# 10_Misc.net
KiCad netlist of a schematic drawn in Altium Designer
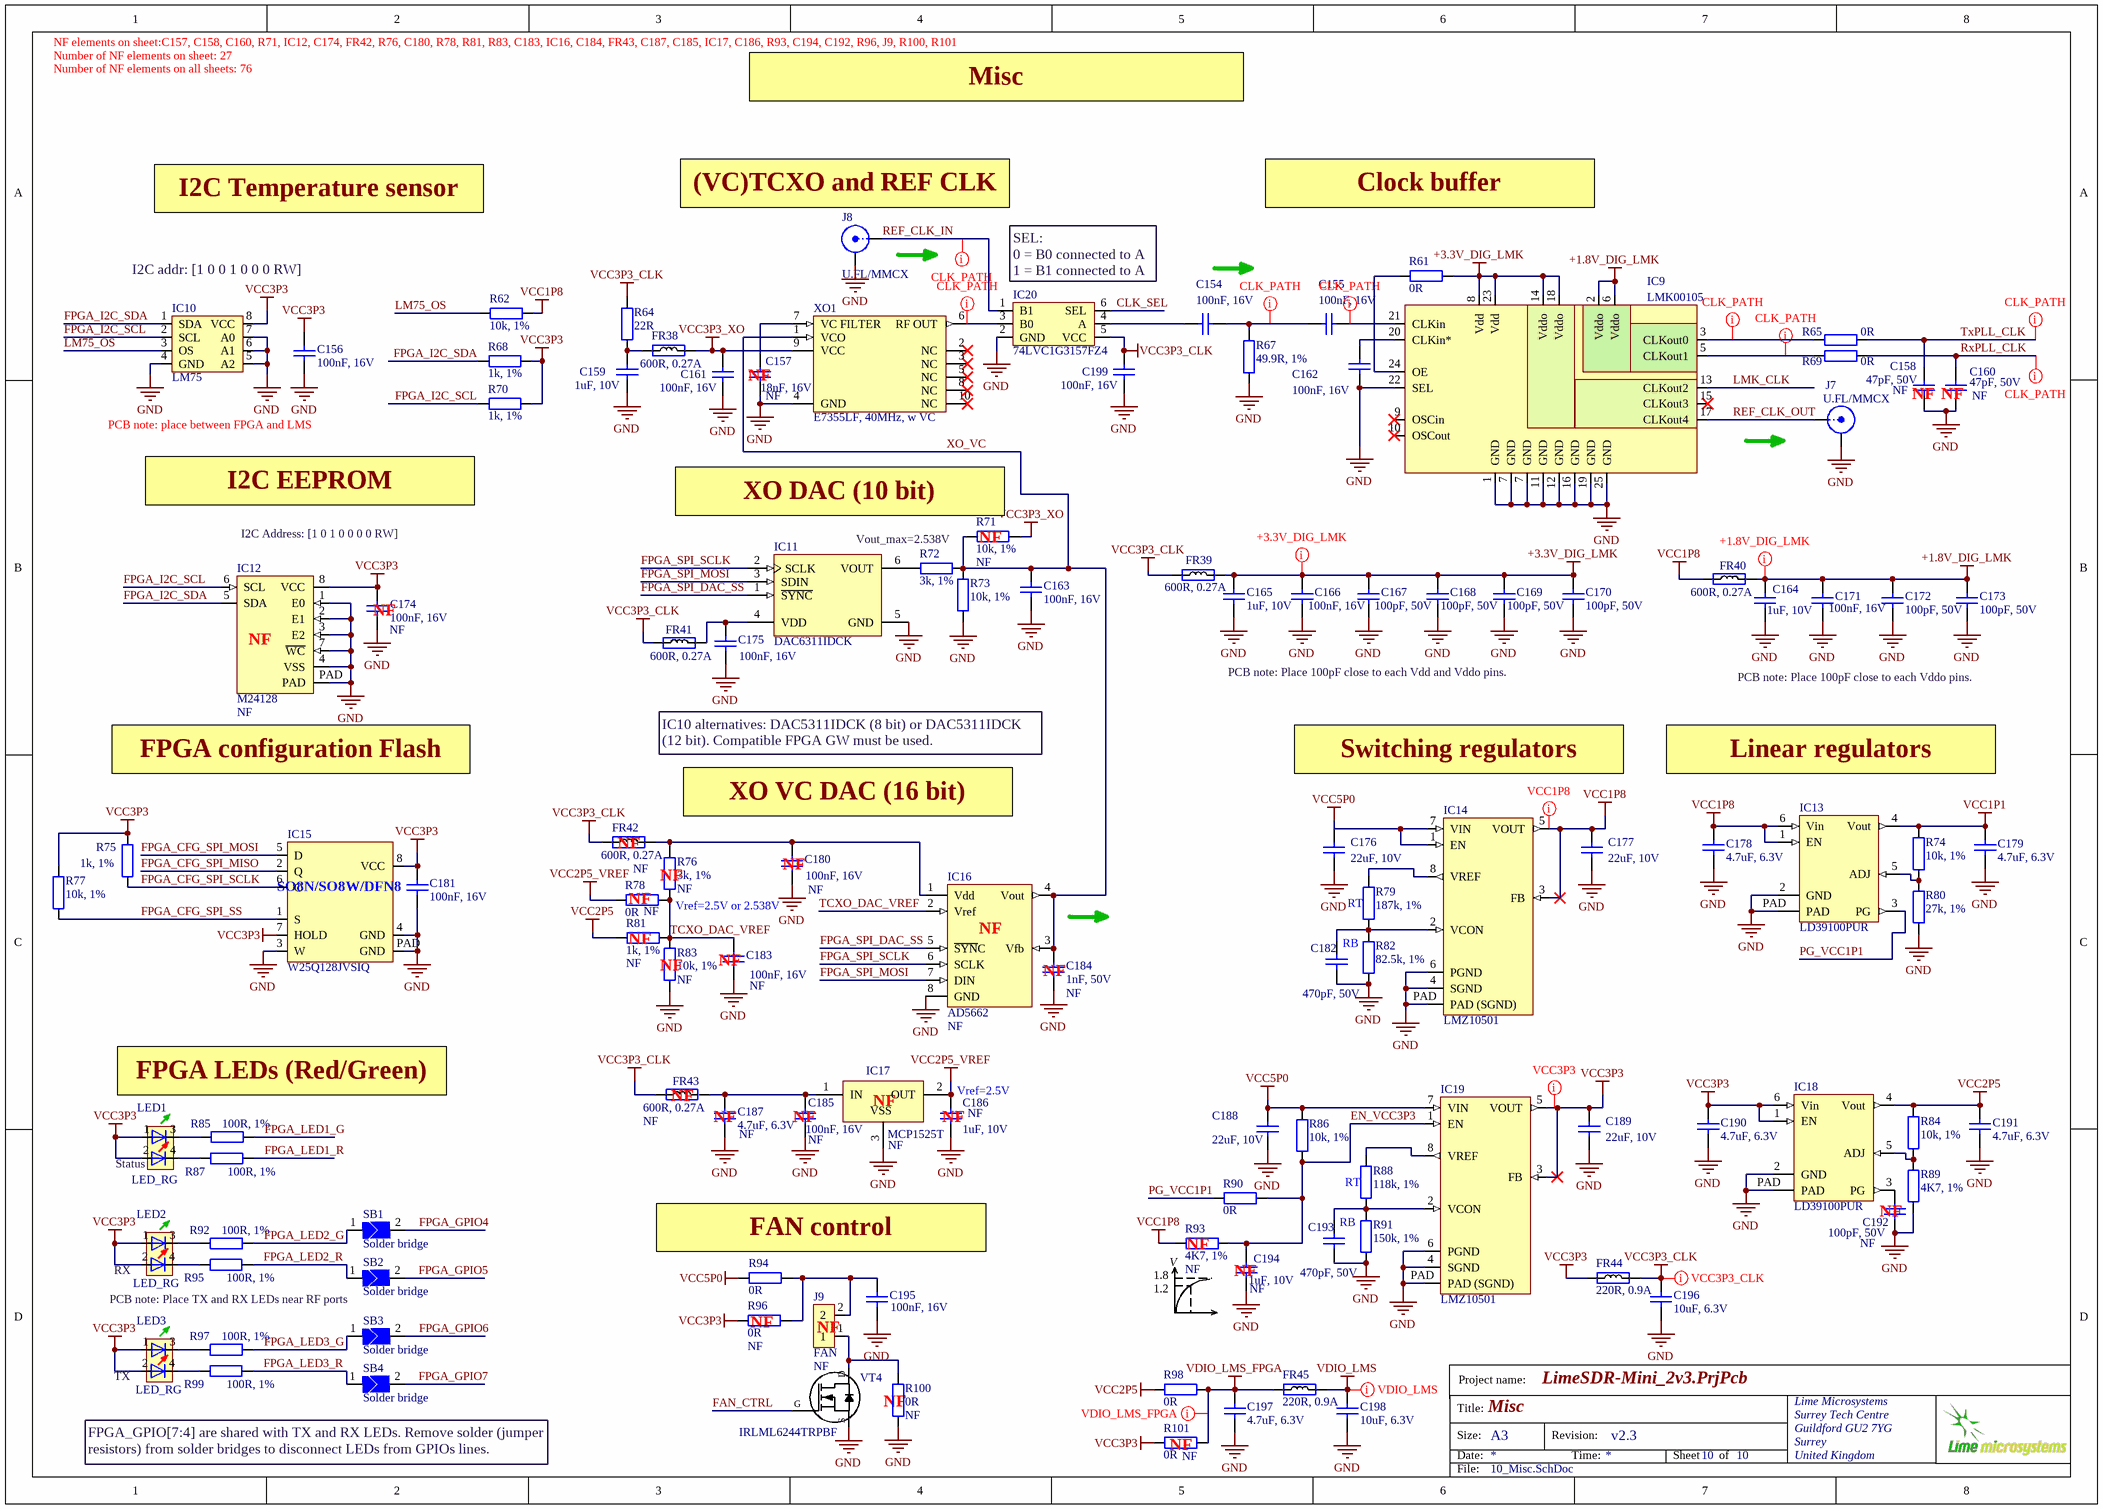
[diagram p0: 10_Misc.SchDoc]

(export (version "E")
  (design (tool "Eeschema 10.0.6"))
  (components
    (comp (ref "C154")
      (value "100nF, 16V")
      (footprint "CAP0402")
      (fields
        (field (name "MANUFACTURER") "Murata Electronics")
        (field (name "TOLERANCE") "10 %")
        (field (name "MANUFACTURER PART NUMBER") "GRM155R71C104KA88D")
      )
      (libsource (lib "LimeMicroAltiumLib_schLib") (part "Cap_0402"))
    )
    (comp (ref "C155")
      (value "100nF, 16V")
      (footprint "CAP0402")
      (fields
        (field (name "MANUFACTURER") "Murata Electronics")
        (field (name "TOLERANCE") "10 %")
        (field (name "MANUFACTURER PART NUMBER") "GRM155R71C104KA88D")
      )
      (libsource (lib "LimeMicroAltiumLib_schLib") (part "Cap_0402"))
    )
    (comp (ref "C156")
      (value "100nF, 16V")
      (footprint "CAP0402")
      (fields
        (field (name "TOLERANCE") "10 %")
        (field (name "MANUFACTURER") "Murata Electronics")
        (field (name "MANUFACTURER PART NUMBER") "GRM155R71C104KA88D")
      )
      (libsource (lib "LimeFPGAboard_schLib") (part "Cap_0603"))
    )
    (comp (ref "C157")
      (value "18nF, 16V")
      (footprint "CAP0402")
      (fields
        (field (name "ASSEMBLY INFO") "NF")
        (field (name "MANUFACTURER") "Yageo")
        (field (name "TOLERANCE") "±10%")
      )
      (libsource (lib "LimeMicroAltiumLib_schLib") (part "Cap_0402"))
    )
    (comp (ref "C158")
      (value "47pF, 50V")
      (footprint "CAP0402")
      (fields
        (field (name "TOLERANCE") "±1%")
        (field (name "MANUFACTURER") "TDK Corporation")
        (field (name "ASSEMBLY INFO") "NF")
      )
      (libsource (lib "LimeMicroAltiumLib_schLib") (part "Cap_0402"))
    )
    (comp (ref "C159")
      (value "1uF, 10V")
      (footprint "CAP0402")
      (fields (field (name "MANUFACTURER") "TDK"))
      (libsource (lib "LimeMicroAltiumLib_schLib") (part "Cap_0402"))
    )
    (comp (ref "C160")
      (value "47pF, 50V")
      (footprint "CAP0402")
      (fields
        (field (name "TOLERANCE") "±1%")
        (field (name "MANUFACTURER") "TDK Corporation")
        (field (name "ASSEMBLY INFO") "NF")
      )
      (libsource (lib "LimeMicroAltiumLib_schLib") (part "Cap_0402"))
    )
    (comp (ref "C161")
      (value "100nF, 16V")
      (footprint "CAP0402")
      (fields
        (field (name "MANUFACTURER") "Murata Electronics")
        (field (name "TOLERANCE") "10 %")
        (field (name "MANUFACTURER PART NUMBER") "GRM155R71C104KA88D")
      )
      (libsource (lib "LimeMicroAltiumLib_schLib") (part "Cap_0402"))
    )
    (comp (ref "C162")
      (value "100nF, 16V")
      (footprint "CAP0402")
      (fields
        (field (name "MANUFACTURER") "Murata Electronics")
        (field (name "TOLERANCE") "10 %")
        (field (name "MANUFACTURER PART NUMBER") "GRM155R71C104KA88D")
      )
      (libsource (lib "LimeMicroAltiumLib_schLib") (part "Cap_0402"))
    )
    (comp (ref "C163")
      (value "100nF, 16V")
      (footprint "CAP0402")
      (fields
        (field (name "MANUFACTURER") "Murata Electronics")
        (field (name "TOLERANCE") "10 %")
        (field (name "MANUFACTURER PART NUMBER") "GRM155R71C104KA88D")
      )
      (libsource (lib "LimeMicroAltiumLib_schLib") (part "Cap_0402"))
    )
    (comp (ref "C164")
      (value "1uF, 10V")
      (footprint "CAP0402")
      (fields (field (name "MANUFACTURER") "TDK"))
      (libsource (lib "LimeMicroAltiumLib_schLib") (part "Cap_0402"))
    )
    (comp (ref "C165")
      (value "1uF, 10V")
      (footprint "CAP0402")
      (fields (field (name "MANUFACTURER") "TDK"))
      (libsource (lib "LimeMicroAltiumLib_schLib") (part "Cap_0402"))
    )
    (comp (ref "C166")
      (value "100nF, 16V")
      (footprint "CAP0402")
      (fields
        (field (name "MANUFACTURER") "Murata Electronics")
        (field (name "TOLERANCE") "10 %")
        (field (name "MANUFACTURER PART NUMBER") "GRM155R71C104KA88D")
      )
      (libsource (lib "LimeMicroAltiumLib_schLib") (part "Cap_0402"))
    )
    (comp (ref "C167")
      (value "100pF, 50V")
      (footprint "CAP0402")
      (fields (field (name "MANUFACTURER") "Yageo") (field (name "TOLERANCE") "±5%"))
      (libsource (lib "LimeMicroAltiumLib_schLib") (part "Cap_0402"))
    )
    (comp (ref "C168")
      (value "100pF, 50V")
      (footprint "CAP0402")
      (fields (field (name "MANUFACTURER") "Yageo") (field (name "TOLERANCE") "±5%"))
      (libsource (lib "LimeMicroAltiumLib_schLib") (part "Cap_0402"))
    )
    (comp (ref "C169")
      (value "100pF, 50V")
      (footprint "CAP0402")
      (fields (field (name "MANUFACTURER") "Yageo") (field (name "TOLERANCE") "±5%"))
      (libsource (lib "LimeMicroAltiumLib_schLib") (part "Cap_0402"))
    )
    (comp (ref "C170")
      (value "100pF, 50V")
      (footprint "CAP0402")
      (fields (field (name "MANUFACTURER") "Yageo") (field (name "TOLERANCE") "±5%"))
      (libsource (lib "LimeMicroAltiumLib_schLib") (part "Cap_0402"))
    )
    (comp (ref "C171")
      (value "100nF, 16V")
      (footprint "CAP0402")
      (fields
        (field (name "MANUFACTURER") "Murata Electronics")
        (field (name "TOLERANCE") "10 %")
        (field (name "MANUFACTURER PART NUMBER") "GRM155R71C104KA88D")
      )
      (libsource (lib "LimeMicroAltiumLib_schLib") (part "Cap_0402"))
    )
    (comp (ref "C172")
      (value "100pF, 50V")
      (footprint "CAP0402")
      (fields (field (name "MANUFACTURER") "Yageo") (field (name "TOLERANCE") "±5%"))
      (libsource (lib "LimeMicroAltiumLib_schLib") (part "Cap_0402"))
    )
    (comp (ref "C173")
      (value "100pF, 50V")
      (footprint "CAP0402")
      (fields (field (name "MANUFACTURER") "Yageo") (field (name "TOLERANCE") "±5%"))
      (libsource (lib "LimeMicroAltiumLib_schLib") (part "Cap_0402"))
    )
    (comp (ref "C174")
      (value "100nF, 16V")
      (footprint "CAP0402")
      (fields
        (field (name "TOLERANCE") "10 %")
        (field (name "MANUFACTURER") "Murata Electronics")
        (field (name "MANUFACTURER PART NUMBER") "GRM155R71C104KA88D")
        (field (name "ASSEMBLY INFO") "NF")
      )
      (libsource (lib "LimeFPGAboard_schLib") (part "Cap_0603"))
    )
    (comp (ref "C175")
      (value "100nF, 16V")
      (footprint "CAP0402")
      (fields
        (field (name "TOLERANCE") "10 %")
        (field (name "MANUFACTURER") "Murata Electronics")
        (field (name "MANUFACTURER PART NUMBER") "GRM155R71C104KA88D")
      )
      (libsource (lib "LimeFPGAboard_schLib") (part "Cap_0603"))
    )
    (comp (ref "C176")
      (value "22uF, 10V")
      (footprint "CAP0603")
      (fields (field (name "TOLERANCE") "20 %") (field (name "MANUFACTURER") "TDK Corporation"))
      (libsource (lib "LimeFPGAboard_schLib") (part "Cap_0603"))
    )
    (comp (ref "C177")
      (value "22uF, 10V")
      (footprint "CAP0603")
      (fields (field (name "TOLERANCE") "20 %") (field (name "MANUFACTURER") "TDK Corporation"))
      (libsource (lib "LimeFPGAboard_schLib") (part "Cap_0603"))
    )
    (comp (ref "C178")
      (value "4.7uF, 6.3V")
      (footprint "CAP0402")
      (fields
        (field (name "MANUFACTURER") "Murata Electronics North America")
        (field (name "TOLERANCE") "±20%")
      )
      (libsource (lib "LimeMicroAltiumLib_schLib") (part "Cap_0402"))
    )
    (comp (ref "C179")
      (value "4.7uF, 6.3V")
      (footprint "CAP0402")
      (fields
        (field (name "MANUFACTURER") "Murata Electronics North America")
        (field (name "TOLERANCE") "±20%")
      )
      (libsource (lib "LimeMicroAltiumLib_schLib") (part "Cap_0402"))
    )
    (comp (ref "C180")
      (value "100nF, 16V")
      (footprint "CAP0402")
      (fields
        (field (name "TOLERANCE") "10 %")
        (field (name "MANUFACTURER") "Murata Electronics")
        (field (name "MANUFACTURER PART NUMBER") "GRM155R71C104KA88D")
        (field (name "ASSEMBLY INFO") "NF")
      )
      (libsource (lib "LimeFPGAboard_schLib") (part "Cap_0603"))
    )
    (comp (ref "C181")
      (value "100nF, 16V")
      (footprint "CAP0402")
      (fields
        (field (name "TOLERANCE") "10 %")
        (field (name "MANUFACTURER") "Murata Electronics")
        (field (name "MANUFACTURER PART NUMBER") "GRM155R71C104KA88D")
      )
      (libsource (lib "LimeFPGAboard_schLib") (part "Cap_0603"))
    )
    (comp (ref "C182")
      (value "470pF, 50V")
      (footprint "CAP0402")
      (fields (field (name "TOLERANCE") "±5%") (field (name "MANUFACTURER") "TDK Corporation"))
      (libsource (lib "LimeMicroAltiumLib_schLib") (part "Cap_0402"))
    )
    (comp (ref "C183")
      (value "100nF, 16V")
      (footprint "CAP0402")
      (fields
        (field (name "TOLERANCE") "10 %")
        (field (name "MANUFACTURER") "Murata Electronics")
        (field (name "ASSEMBLY INFO") "NF")
      )
      (libsource (lib "") (part "Cap_0603_1"))
    )
    (comp (ref "C184")
      (value "1nF, 50V")
      (footprint "CAP0402")
      (fields
        (field (name "ASSEMBLY INFO") "NF")
        (field (name "TOLERANCE") "10 %")
        (field (name "MANUFACTURER") "Murata Electronics")
      )
      (libsource (lib "") (part "Cap_0402_1"))
    )
    (comp (ref "C185")
      (value "100nF, 16V")
      (footprint "CAP0402")
      (fields
        (field (name "TOLERANCE") "10 %")
        (field (name "MANUFACTURER") "Murata Electronics")
        (field (name "ASSEMBLY INFO") "NF")
      )
      (libsource (lib "") (part "Cap_0603_1"))
    )
    (comp (ref "C186")
      (value "1uF, 10V")
      (footprint "CAP0402")
      (fields (field (name "ASSEMBLY INFO") "NF") (field (name "MANUFACTURER") "TDK"))
      (libsource (lib "LimeMicroAltiumLib_schLib") (part "Cap_0402"))
    )
    (comp (ref "C187")
      (value "4.7uF, 6.3V")
      (footprint "CAP0402")
      (fields
        (field (name "ASSEMBLY INFO") "NF")
        (field (name "MANUFACTURER") "Murata Electronics North America")
        (field (name "TOLERANCE") "±20%")
      )
      (libsource (lib "LimeMicroAltiumLib_schLib") (part "Cap_0402"))
    )
    (comp (ref "C188")
      (value "22uF, 10V")
      (footprint "CAP0603")
      (fields (field (name "TOLERANCE") "20 %") (field (name "MANUFACTURER") "TDK Corporation"))
      (libsource (lib "LimeFPGAboard_schLib") (part "Cap_0603"))
    )
    (comp (ref "C189")
      (value "22uF, 10V")
      (footprint "CAP0603")
      (fields (field (name "TOLERANCE") "20 %") (field (name "MANUFACTURER") "TDK Corporation"))
      (libsource (lib "LimeFPGAboard_schLib") (part "Cap_0603"))
    )
    (comp (ref "C190")
      (value "4.7uF, 6.3V")
      (footprint "CAP0402")
      (fields
        (field (name "MANUFACTURER") "Murata Electronics North America")
        (field (name "TOLERANCE") "±20%")
      )
      (libsource (lib "LimeMicroAltiumLib_schLib") (part "Cap_0402"))
    )
    (comp (ref "C191")
      (value "4.7uF, 6.3V")
      (footprint "CAP0402")
      (fields
        (field (name "MANUFACTURER") "Murata Electronics North America")
        (field (name "TOLERANCE") "±20%")
      )
      (libsource (lib "LimeMicroAltiumLib_schLib") (part "Cap_0402"))
    )
    (comp (ref "C192")
      (value "100pF, 50V")
      (footprint "CAP0402")
      (fields
        (field (name "ASSEMBLY INFO") "NF")
        (field (name "MANUFACTURER") "Yageo")
        (field (name "TOLERANCE") "±5%")
      )
      (libsource (lib "LimeMicroAltiumLib_schLib") (part "Cap_0402"))
    )
    (comp (ref "C193")
      (value "470pF, 50V")
      (footprint "CAP0402")
      (fields (field (name "TOLERANCE") "±5%") (field (name "MANUFACTURER") "TDK Corporation"))
      (libsource (lib "LimeMicroAltiumLib_schLib") (part "Cap_0402"))
    )
    (comp (ref "C194")
      (value "1uF, 10V")
      (footprint "CAP0402")
      (fields (field (name "ASSEMBLY INFO") "NF") (field (name "MANUFACTURER") "TDK"))
      (libsource (lib "LimeMicroAltiumLib_schLib") (part "Cap_0402"))
    )
    (comp (ref "C195")
      (value "100nF, 16V")
      (footprint "CAP0402")
      (fields
        (field (name "TOLERANCE") "10 %")
        (field (name "MANUFACTURER") "Murata Electronics")
        (field (name "MANUFACTURER PART NUMBER") "GRM155R71C104KA88D")
      )
      (libsource (lib "LimeFPGAboard_schLib") (part "Cap_0603"))
    )
    (comp (ref "C196")
      (value "10uF, 6.3V")
      (footprint "CAP0603")
      (fields (field (name "TOLERANCE") "±20%") (field (name "MANUFACTURER") "Yageo"))
      (libsource (lib "LimeFPGAboard_schLib") (part "Cap_0603"))
    )
    (comp (ref "C197")
      (value "4.7uF, 6.3V")
      (footprint "CAP0402")
      (fields
        (field (name "MANUFACTURER") "Murata Electronics North America")
        (field (name "TOLERANCE") "±20%")
      )
      (libsource (lib "LimeMicroAltiumLib_schLib") (part "Cap_0402"))
    )
    (comp (ref "C198")
      (value "10uF, 6.3V")
      (footprint "CAP0603")
      (fields (field (name "TOLERANCE") "±20%") (field (name "MANUFACTURER") "Yageo"))
      (libsource (lib "LimeFPGAboard_schLib") (part "Cap_0603"))
    )
    (comp (ref "C199")
      (value "100nF, 16V")
      (footprint "CAP0402")
      (fields
        (field (name "MANUFACTURER") "Murata Electronics")
        (field (name "TOLERANCE") "10 %")
        (field (name "MANUFACTURER PART NUMBER") "GRM155R71C104KA88D")
      )
      (libsource (lib "LimeMicroAltiumLib_schLib") (part "Cap_0402"))
    )
    (comp (ref "FR38")
      (value "600R, 0.27A")
      (footprint "RES0201")
      (fields (field (name "MANUFACTURER") "Taiyo Yuden"))
      (libsource (lib "LimeMicroAltiumLib_schLib") (part "Ferrite"))
    )
    (comp (ref "FR39")
      (value "600R, 0.27A")
      (footprint "RES0201")
      (fields (field (name "MANUFACTURER") "Taiyo Yuden"))
      (libsource (lib "LimeMicroAltiumLib_schLib") (part "Ferrite"))
    )
    (comp (ref "FR40")
      (value "600R, 0.27A")
      (footprint "RES0201")
      (fields (field (name "MANUFACTURER") "Taiyo Yuden"))
      (libsource (lib "LimeMicroAltiumLib_schLib") (part "Ferrite"))
    )
    (comp (ref "FR41")
      (value "600R, 0.27A")
      (footprint "RES0201")
      (fields (field (name "MANUFACTURER") "Taiyo Yuden"))
      (libsource (lib "LimeMicroAltiumLib_schLib") (part "Ferrite"))
    )
    (comp (ref "FR42")
      (value "600R, 0.27A")
      (footprint "RES0201")
      (fields (field (name "MANUFACTURER") "Taiyo Yuden") (field (name "ASSEMBLY INFO") "NF"))
      (libsource (lib "LimeMicroAltiumLib_schLib") (part "Ferrite"))
    )
    (comp (ref "FR43")
      (value "600R, 0.27A")
      (footprint "RES0201")
      (fields (field (name "MANUFACTURER") "Taiyo Yuden") (field (name "ASSEMBLY INFO") "NF"))
      (libsource (lib "LimeMicroAltiumLib_schLib") (part "Ferrite"))
    )
    (comp (ref "FR44")
      (value "220R, 0.9A")
      (footprint "RES0402")
      (fields (field (name "MANUFACTURER") "TDK Corporation"))
      (libsource (lib "LimeFPGAboard_schLib") (part "Ferrite"))
    )
    (comp (ref "FR45")
      (value "220R, 0.9A")
      (footprint "RES0402")
      (fields (field (name "MANUFACTURER") "TDK Corporation"))
      (libsource (lib "LimeFPGAboard_schLib") (part "Ferrite"))
    )
    (comp (ref "IC9")
      (value "LMK00105")
      (footprint "LMK00105SQ")
      (fields (field (name "MANUFACTURER") "Texas Instruments"))
      (libsource (lib "LimeMicroAltiumLib_schLib") (part "LMK00105"))
    )
    (comp (ref "IC10")
      (value "LM75")
      (footprint "HWSON8_LM75")
      (fields (field (name "MANUFACTURER") "NXP Semiconductors"))
      (libsource (lib "LimeMicroAltiumLib_schLib") (part "LM75"))
    )
    (comp (ref "IC11")
      (value "DAC6311IDCK")
      (footprint "AD5601_SOT23-6")
      (fields (field (name "MANUFACTURER") "Texas Instruments"))
      (libsource (lib "LimeMicroAltiumLib_schLib") (part "AD5601BKSZ-REEL7"))
    )
    (comp (ref "IC12")
      (value "M24128")
      (footprint "M24128-DFMC6TG")
      (fields (field (name "MANUFACTURER") "STMicroelectronics") (field (name "ASSEMBLY INFO") "NF"))
      (libsource (lib "LimeMicroAltiumLib_schLib") (part "M24128-DFMC6TG"))
    )
    (comp (ref "IC13")
      (value "LD39100PUR")
      (footprint "LD39100PUR")
      (fields (field (name "MANUFACTURER") "STMicroelectronics"))
      (libsource (lib "LimeMicroAltiumLib_schLib") (part "LD39100PUR"))
    )
    (comp (ref "IC14")
      (value "LMZ10501")
      (footprint "LMZ10501")
      (fields (field (name "MANUFACTURER") "Texas Instruments"))
      (libsource (lib "LimeMicroAltiumLib_schLib") (part "LMZ10501"))
    )
    (comp (ref "IC15")
      (value "W25Q128JVSIQ")
      (footprint "S25FL164K_WSON8_DFN6")
      (fields (field (name "MANUFACTURER") "Winbond"))
      (libsource (lib "LimeMicroAltiumLib_schLib_r03") (part "M25P40_with_pad"))
    )
    (comp (ref "IC16")
      (value "AD5662")
      (footprint "AD5662_SOT23-8")
      (fields (field (name "MANUFACTURER") "Analog Devices Inc.") (field (name "ASSEMBLY INFO") "NF"))
      (libsource (lib "LimeMicroAltiumLib_schLib") (part "AD5662"))
    )
    (comp (ref "IC17")
      (value "MCP1525T")
      (footprint "SOT23-3_v2")
      (description "2.5V Voltage Reference, 3-Pin SOT-23, Industrial Temperature, Tape and Reel")
      (fields
        (field (name "MANUFACTURER") "Microchip Technology")
        (field (name "TOLERANCE") "±1%")
        (field (name "ASSEMBLY INFO") "NF")
      )
      (libsource (lib "LimeMicroAltiumLib_schLib") (part "MCP1525T-I/TT"))
    )
    (comp (ref "IC18")
      (value "LD39100PUR")
      (footprint "LD39100PUR")
      (fields (field (name "MANUFACTURER") "STMicroelectronics"))
      (libsource (lib "LimeMicroAltiumLib_schLib") (part "LD39100PUR"))
    )
    (comp (ref "IC19")
      (value "LMZ10501")
      (footprint "LMZ10501")
      (fields (field (name "MANUFACTURER") "Texas Instruments"))
      (libsource (lib "LimeMicroAltiumLib_schLib") (part "LMZ10501"))
    )
    (comp (ref "IC20")
      (value "74LVC1G3157FZ4")
      (footprint "74LVC1G3157FZ4_SPDT_SW_DFN1410-6")
      (fields (field (name "MANUFACTURER") "Diodes"))
      (libsource (lib "LimeMicroAltiumLib_schLib_r04") (part "74LVC1G3157FZ4_SPDT_SW"))
    )
    (comp (ref "J7")
      (value "U.FL/MMCX")
      (footprint "MMCX_UFL_conn_u")
      (description "CONN UMC RCPT STR 50 OHM SMD")
      (fields (field (name "MANUFACTURER") "Molex, LLC"))
      (libsource (lib "LimeMicroAltiumLib_schLib") (part "RF_IF_connector"))
    )
    (comp (ref "J8")
      (value "U.FL/MMCX")
      (footprint "MMCX_UFL_conn_u")
      (description "CONN UMC RCPT STR 50 OHM SMD")
      (fields (field (name "MANUFACTURER") "Molex, LLC"))
      (libsource (lib "LimeMicroAltiumLib_schLib") (part "RF_IF_connector"))
    )
    (comp (ref "J9")
      (value "FAN")
      (footprint "Header2x1_TH_v2")
      (fields (field (name "ASSEMBLY INFO") "NF") (field (name "MANUFACTURER") "3M"))
      (libsource (lib "LimeFPGAboard_schLib") (part "Jumper"))
    )
    (comp (ref "LED1")
      (value "LED_RG")
      (footprint "LED-2x0603")
      (fields (field (name "MANUFACTURER") "Avago Technologies US Inc."))
      (libsource (lib "LimeMicroAltiumLib_schLib") (part "LED_green_red_SMD"))
    )
    (comp (ref "LED2")
      (value "LED_RG")
      (footprint "LED-2x0603")
      (fields (field (name "MANUFACTURER") "Avago Technologies US Inc."))
      (libsource (lib "LimeMicroAltiumLib_schLib") (part "LED_green_red_SMD"))
    )
    (comp (ref "LED3")
      (value "LED_RG")
      (footprint "LED-2x0603")
      (fields (field (name "MANUFACTURER") "Avago Technologies US Inc."))
      (libsource (lib "LimeMicroAltiumLib_schLib") (part "LED_green_red_SMD"))
    )
    (comp (ref "R61")
      (value "0R")
      (footprint "RES0402")
      (fields (field (name "MANUFACTURER") "Yageo") (field (name "TOLERANCE") "Jumper"))
      (libsource (lib "LimeMicroAltiumLib_schLib") (part "Res_0402"))
    )
    (comp (ref "R62")
      (value "10k, 1%")
      (footprint "RES0402")
      (fields (field (name "MANUFACTURER") "Yageo") (field (name "TOLERANCE") "±1%"))
      (libsource (lib "LimeMicroAltiumLib_schLib") (part "Res_0402"))
    )
    (comp (ref "R64")
      (value "22R")
      (footprint "RES0402")
      (fields (field (name "TOLERANCE") "±1%") (field (name "MANUFACTURER") "Yageo"))
      (libsource (lib "LimeFPGAboard_schLib") (part "Res_0402"))
    )
    (comp (ref "R65")
      (value "0R")
      (footprint "RES0402")
      (fields (field (name "MANUFACTURER") "Yageo") (field (name "TOLERANCE") "Jumper"))
      (libsource (lib "LimeFPGAboard_schLib") (part "Res_0402"))
    )
    (comp (ref "R67")
      (value "49.9R, 1%")
      (footprint "RES0402")
      (fields
        (field (name "TOLERANCE") "±1%")
        (field (name "MANUFACTURER") "Samsung Electro-Mechanics America, Inc.")
      )
      (libsource (lib "LimeMicroAltiumLib_schLib") (part "Res_0402"))
    )
    (comp (ref "R68")
      (value "1k, 1%")
      (footprint "RES0402")
      (fields (field (name "MANUFACTURER") "Stackpole Electronics Inc") (field (name "TOLERANCE") "±1%"))
      (libsource (lib "LimeMicroAltiumLib_schLib") (part "Res_0402"))
    )
    (comp (ref "R69")
      (value "0R")
      (footprint "RES0402")
      (fields (field (name "MANUFACTURER") "Yageo") (field (name "TOLERANCE") "Jumper"))
      (libsource (lib "LimeFPGAboard_schLib") (part "Res_0402"))
    )
    (comp (ref "R70")
      (value "1k, 1%")
      (footprint "RES0402")
      (fields (field (name "MANUFACTURER") "Stackpole Electronics Inc") (field (name "TOLERANCE") "±1%"))
      (libsource (lib "LimeMicroAltiumLib_schLib") (part "Res_0402"))
    )
    (comp (ref "R71")
      (value "10k, 1%")
      (footprint "RES0402")
      (fields
        (field (name "ASSEMBLY INFO") "NF")
        (field (name "MANUFACTURER") "Yageo")
        (field (name "TOLERANCE") "±1%")
      )
      (libsource (lib "LimeMicroAltiumLib_schLib") (part "Res_0402"))
    )
    (comp (ref "R72")
      (value "3k, 1%")
      (footprint "RES0402")
      (fields (field (name "TOLERANCE") "±1%") (field (name "MANUFACTURER") "Vishay Dale"))
      (libsource (lib "LimeMicroAltiumLib_schLib") (part "Res_0402"))
    )
    (comp (ref "R73")
      (value "10k, 1%")
      (footprint "RES0402")
      (fields (field (name "MANUFACTURER") "Yageo") (field (name "TOLERANCE") "±1%"))
      (libsource (lib "LimeMicroAltiumLib_schLib") (part "Res_0402"))
    )
    (comp (ref "R74")
      (value "10k, 1%")
      (footprint "RES0402")
      (fields (field (name "MANUFACTURER") "Yageo") (field (name "TOLERANCE") "±1%"))
      (libsource (lib "LimeMicroAltiumLib_schLib") (part "Res_0402"))
    )
    (comp (ref "R75")
      (value "1k, 1%")
      (footprint "RES0402")
      (fields (field (name "MANUFACTURER") "Stackpole Electronics Inc") (field (name "TOLERANCE") "±1%"))
      (libsource (lib "LimeMicroAltiumLib_schLib") (part "Res_0402"))
    )
    (comp (ref "R76")
      (value "3k, 1%")
      (footprint "RES0402")
      (fields
        (field (name "ASSEMBLY INFO") "NF")
        (field (name "TOLERANCE") "±1%")
        (field (name "MANUFACTURER") "Vishay Dale")
      )
      (libsource (lib "") (part "Res_0402_1"))
    )
    (comp (ref "R77")
      (value "10k, 1%")
      (footprint "RES0402")
      (fields (field (name "MANUFACTURER") "Yageo") (field (name "TOLERANCE") "±1%"))
      (libsource (lib "LimeMicroAltiumLib_schLib") (part "Res_0402"))
    )
    (comp (ref "R78")
      (value "0R")
      (footprint "RES0402")
      (fields
        (field (name "ASSEMBLY INFO") "NF")
        (field (name "MANUFACTURER") "Yageo")
        (field (name "TOLERANCE") "Jumper")
      )
      (libsource (lib "LimeMicroAltiumLib_schLib") (part "Res_0402"))
    )
    (comp (ref "R79")
      (value "187k, 1%")
      (footprint "RES0402")
      (fields (field (name "TOLERANCE") "±1%") (field (name "MANUFACTURER") "Yageo"))
      (libsource (lib "LimeMicroAltiumLib_schLib") (part "Res_0402"))
    )
    (comp (ref "R80")
      (value "27k, 1%")
      (footprint "RES0402")
      (fields (field (name "MANUFACTURER") "Yageo") (field (name "TOLERANCE") "1%"))
      (libsource (lib "LimeFPGAboard_schLib") (part "Res_0402"))
    )
    (comp (ref "R81")
      (value "1k, 1%")
      (footprint "RES0402")
      (fields
        (field (name "ASSEMBLY INFO") "NF")
        (field (name "MANUFACTURER") "Stackpole Electronics Inc")
        (field (name "TOLERANCE") "±1%")
      )
      (libsource (lib "") (part "Res_0402_1"))
    )
    (comp (ref "R82")
      (value "82.5k, 1%")
      (footprint "RES0402")
      (fields (field (name "TOLERANCE") "±1%") (field (name "MANUFACTURER") "Yageo"))
      (libsource (lib "LimeMicroAltiumLib_schLib") (part "Res_0402"))
    )
    (comp (ref "R83")
      (value "10k, 1%")
      (footprint "RES0402")
      (fields
        (field (name "ASSEMBLY INFO") "NF")
        (field (name "MANUFACTURER") "Yageo")
        (field (name "TOLERANCE") "±1%")
      )
      (libsource (lib "") (part "Res_0402_1"))
    )
    (comp (ref "R84")
      (value "10k, 1%")
      (footprint "RES0402")
      (fields (field (name "MANUFACTURER") "Yageo") (field (name "TOLERANCE") "±1%"))
      (libsource (lib "LimeMicroAltiumLib_schLib") (part "Res_0402"))
    )
    (comp (ref "R85")
      (value "100R, 1%")
      (footprint "RES0402")
      (fields (field (name "TOLERANCE") "±1%") (field (name "MANUFACTURER") "Stackpole Electronics Inc."))
      (libsource (lib "LimeMicroAltiumLib_schLib") (part "Res_0402"))
    )
    (comp (ref "R86")
      (value "10k, 1%")
      (footprint "RES0402")
      (fields (field (name "MANUFACTURER") "Yageo") (field (name "TOLERANCE") "±1%"))
      (libsource (lib "LimeMicroAltiumLib_schLib") (part "Res_0402"))
    )
    (comp (ref "R87")
      (value "100R, 1%")
      (footprint "RES0402")
      (fields (field (name "TOLERANCE") "±1%") (field (name "MANUFACTURER") "Stackpole Electronics Inc."))
      (libsource (lib "LimeMicroAltiumLib_schLib") (part "Res_0402"))
    )
    (comp (ref "R88")
      (value "118k, 1%")
      (footprint "RES0402")
      (fields (field (name "MANUFACTURER") "Yageo") (field (name "TOLERANCE") "±1%"))
      (libsource (lib "LimeMicroAltiumLib_schLib") (part "Res_0402"))
    )
    (comp (ref "R89")
      (value "4K7, 1%")
      (footprint "RES0402")
      (fields (field (name "MANUFACTURER") "Yageo") (field (name "TOLERANCE") "±1%"))
      (libsource (lib "LimeFPGAboard_schLib") (part "Res_0402"))
    )
    (comp (ref "R90")
      (value "0R")
      (footprint "RES0402")
      (fields (field (name "MANUFACTURER") "Yageo") (field (name "TOLERANCE") "Jumper"))
      (libsource (lib "LimeMicroAltiumLib_schLib") (part "Res_0402"))
    )
    (comp (ref "R91")
      (value "150k, 1%")
      (footprint "RES0402")
      (fields (field (name "TOLERANCE") "1%"))
      (libsource (lib "LimeMicroAltiumLib_schLib") (part "Res_0402"))
    )
    (comp (ref "R92")
      (value "100R, 1%")
      (footprint "RES0402")
      (fields (field (name "TOLERANCE") "±1%") (field (name "MANUFACTURER") "Stackpole Electronics Inc."))
      (libsource (lib "LimeMicroAltiumLib_schLib") (part "Res_0402"))
    )
    (comp (ref "R93")
      (value "4K7, 1%")
      (footprint "RES0402")
      (fields
        (field (name "MANUFACTURER") "Yageo")
        (field (name "TOLERANCE") "±1%")
        (field (name "ASSEMBLY INFO") "NF")
      )
      (libsource (lib "LimeFPGAboard_schLib") (part "Res_0402"))
    )
    (comp (ref "R94")
      (value "0R")
      (footprint "RES0402")
      (fields (field (name "MANUFACTURER") "Yageo") (field (name "TOLERANCE") "Jumper"))
      (libsource (lib "LimeMicroAltiumLib_schLib") (part "Res_0402"))
    )
    (comp (ref "R95")
      (value "100R, 1%")
      (footprint "RES0402")
      (fields (field (name "TOLERANCE") "±1%") (field (name "MANUFACTURER") "Stackpole Electronics Inc."))
      (libsource (lib "LimeMicroAltiumLib_schLib") (part "Res_0402"))
    )
    (comp (ref "R96")
      (value "0R")
      (footprint "RES0402")
      (fields
        (field (name "ASSEMBLY INFO") "NF")
        (field (name "MANUFACTURER") "Yageo")
        (field (name "TOLERANCE") "Jumper")
      )
      (libsource (lib "LimeMicroAltiumLib_schLib") (part "Res_0402"))
    )
    (comp (ref "R97")
      (value "100R, 1%")
      (footprint "RES0402")
      (fields (field (name "TOLERANCE") "±1%") (field (name "MANUFACTURER") "Stackpole Electronics Inc."))
      (libsource (lib "LimeMicroAltiumLib_schLib") (part "Res_0402"))
    )
    (comp (ref "R98")
      (value "0R")
      (footprint "RES0402")
      (fields (field (name "MANUFACTURER") "Yageo") (field (name "TOLERANCE") "Jumper"))
      (libsource (lib "LimeFPGAboard_schLib") (part "Res_0402"))
    )
    (comp (ref "R99")
      (value "100R, 1%")
      (footprint "RES0402")
      (fields (field (name "TOLERANCE") "±1%") (field (name "MANUFACTURER") "Stackpole Electronics Inc."))
      (libsource (lib "LimeMicroAltiumLib_schLib") (part "Res_0402"))
    )
    (comp (ref "R100")
      (value "0R")
      (footprint "RES0402")
      (fields
        (field (name "ASSEMBLY INFO") "NF")
        (field (name "MANUFACTURER") "Yageo")
        (field (name "TOLERANCE") "Jumper")
      )
      (libsource (lib "LimeMicroAltiumLib_schLib") (part "Res_0402"))
    )
    (comp (ref "R101")
      (value "0R")
      (footprint "RES0402")
      (fields
        (field (name "MANUFACTURER") "Yageo")
        (field (name "ASSEMBLY INFO") "NF")
        (field (name "TOLERANCE") "Jumper")
      )
      (libsource (lib "LimeFPGAboard_schLib") (part "Res_0402"))
    )
    (comp (ref "SB1")
      (value "Solder bridge")
      (footprint "SOLDER_BRIDGE_TRIANGULAR_v2")
      (description "Can be shorted out using solder paste or 0402-1206 resistor")
      (fields (field (name "MANUFACTURER") "Yageo") (field (name "TOLERANCE") "Jumper"))
      (libsource (lib "LimeMicroAltiumLib_schLib_r03") (part "SOLDER_BRIDGE_TRIANGULAR"))
    )
    (comp (ref "SB2")
      (value "Solder bridge")
      (footprint "SOLDER_BRIDGE_TRIANGULAR_v2")
      (description "Can be shorted out using solder paste or 0402-1206 resistor")
      (fields (field (name "MANUFACTURER") "Yageo") (field (name "TOLERANCE") "Jumper"))
      (libsource (lib "LimeMicroAltiumLib_schLib_r03") (part "SOLDER_BRIDGE_TRIANGULAR"))
    )
    (comp (ref "SB3")
      (value "Solder bridge")
      (footprint "SOLDER_BRIDGE_TRIANGULAR_v2")
      (description "Can be shorted out using solder paste or 0402-1206 resistor")
      (fields (field (name "MANUFACTURER") "Yageo") (field (name "TOLERANCE") "Jumper"))
      (libsource (lib "LimeMicroAltiumLib_schLib_r03") (part "SOLDER_BRIDGE_TRIANGULAR"))
    )
    (comp (ref "SB4")
      (value "Solder bridge")
      (footprint "SOLDER_BRIDGE_TRIANGULAR_v2")
      (description "Can be shorted out using solder paste or 0402-1206 resistor")
      (fields (field (name "MANUFACTURER") "Yageo") (field (name "TOLERANCE") "Jumper"))
      (libsource (lib "LimeMicroAltiumLib_schLib_r03") (part "SOLDER_BRIDGE_TRIANGULAR"))
    )
    (comp (ref "VT4")
      (value "IRLML6244TRPBF")
      (footprint "SOT23-3")
      (description "NDS331N")
      (fields (field (name "MANUFACTURER") "Infineon Technologies"))
      (libsource (lib "LimeFPGAboard_schLib") (part "NDS331N"))
    )
    (comp (ref "XO1")
      (value "E7355LF, 40MHz, w VC")
      (footprint "RAKON_RTX5032A")
      (fields (field (name "MANUFACTURER") "Rakon"))
      (libsource (lib "LimeMicroAltiumLib_schLib") (part "Rakon_RTX5032A"))
    )
  )
  (nets
    (net (code "1") (name "+1.8V_DIG_LMK") (class "Default")
      (node (ref "C164") (pin "2") (pinfunction "2_2") (pintype "passive"))
      (node (ref "C171") (pin "2") (pinfunction "2_2") (pintype "passive"))
      (node (ref "C172") (pin "2") (pinfunction "2_2") (pintype "passive"))
      (node (ref "C173") (pin "2") (pinfunction "2_2") (pintype "passive"))
      (node (ref "FR40") (pin "2") (pinfunction "2_2") (pintype "passive"))
      (node (ref "IC9") (pin "2") (pinfunction "Vddo_2") (pintype "passive"))
      (node (ref "IC9") (pin "6") (pinfunction "Vddo_6") (pintype "passive"))
    )
    (net (code "2") (name "+3.3V_DIG_LMK") (class "Default")
      (node (ref "C165") (pin "2") (pinfunction "2_2") (pintype "passive"))
      (node (ref "C166") (pin "2") (pinfunction "2_2") (pintype "passive"))
      (node (ref "C167") (pin "2") (pinfunction "2_2") (pintype "passive"))
      (node (ref "C168") (pin "2") (pinfunction "2_2") (pintype "passive"))
      (node (ref "C169") (pin "2") (pinfunction "2_2") (pintype "passive"))
      (node (ref "C170") (pin "2") (pinfunction "2_2") (pintype "passive"))
      (node (ref "FR39") (pin "2") (pinfunction "2_2") (pintype "passive"))
      (node (ref "IC9") (pin "14") (pinfunction "Vddo_14") (pintype "passive"))
      (node (ref "IC9") (pin "18") (pinfunction "Vddo_18") (pintype "passive"))
      (node (ref "IC9") (pin "23") (pinfunction "Vdd_23") (pintype "passive"))
      (node (ref "IC9") (pin "8") (pinfunction "Vdd_8") (pintype "passive"))
      (node (ref "R61") (pin "2") (pinfunction "2_2") (pintype "passive"))
    )
    (net (code "3") (name "/CLK_SEL") (class "Default")
      (node (ref "IC20") (pin "6") (pinfunction "SEL_6") (pintype "passive"))
    )
    (net (code "4") (name "/EN_VCC3P3") (class "Default")
      (node (ref "C194") (pin "2") (pinfunction "2_2") (pintype "passive"))
      (node (ref "IC19") (pin "1") (pinfunction "EN_1") (pintype "input"))
      (node (ref "R86") (pin "1") (pinfunction "1_1") (pintype "passive"))
      (node (ref "R90") (pin "2") (pinfunction "2_2") (pintype "passive"))
      (node (ref "R93") (pin "1") (pinfunction "1_1") (pintype "passive"))
    )
    (net (code "5") (name "/FAN_CTRL") (class "Default")
      (node (ref "VT4") (pin "G") (pinfunction "G_G") (pintype "passive"))
    )
    (net (code "6") (name "/FPGA_CFG_SPI_MISO") (class "Default")
      (node (ref "IC15") (pin "2") (pinfunction "Q_2") (pintype "passive"))
    )
    (net (code "7") (name "/FPGA_CFG_SPI_MOSI") (class "Default")
      (node (ref "IC15") (pin "5") (pinfunction "D_5") (pintype "passive"))
    )
    (net (code "8") (name "/FPGA_CFG_SPI_SCLK") (class "Default")
      (node (ref "IC15") (pin "6") (pinfunction "C_6") (pintype "passive"))
      (node (ref "R75") (pin "1") (pinfunction "1_1") (pintype "passive"))
    )
    (net (code "9") (name "/FPGA_CFG_SPI_SS") (class "Default")
      (node (ref "IC15") (pin "1") (pinfunction "S_1") (pintype "passive"))
      (node (ref "R77") (pin "1") (pinfunction "1_1") (pintype "passive"))
    )
    (net (code "10") (name "/FPGA_GPIO4") (class "Default")
      (node (ref "SB1") (pin "2") (pinfunction "2_2") (pintype "passive"))
    )
    (net (code "11") (name "/FPGA_GPIO5") (class "Default")
      (node (ref "SB2") (pin "2") (pinfunction "2_2") (pintype "passive"))
    )
    (net (code "12") (name "/FPGA_GPIO6") (class "Default")
      (node (ref "SB3") (pin "2") (pinfunction "2_2") (pintype "passive"))
    )
    (net (code "13") (name "/FPGA_GPIO7") (class "Default")
      (node (ref "SB4") (pin "2") (pinfunction "2_2") (pintype "passive"))
    )
    (net (code "14") (name "/FPGA_I2C_SCL") (class "Default")
      (node (ref "IC10") (pin "2") (pinfunction "SCL_2") (pintype "passive"))
      (node (ref "IC12") (pin "6") (pinfunction "SCL_6") (pintype "input"))
      (node (ref "R70") (pin "2") (pinfunction "2_2") (pintype "passive"))
    )
    (net (code "15") (name "/FPGA_I2C_SDA") (class "Default")
      (node (ref "IC10") (pin "1") (pinfunction "SDA_1") (pintype "passive"))
      (node (ref "IC12") (pin "5") (pinfunction "SDA_5") (pintype "bidirectional"))
      (node (ref "R68") (pin "2") (pinfunction "2_2") (pintype "passive"))
    )
    (net (code "16") (name "/FPGA_LED1_G") (class "Default")
      (node (ref "R85") (pin "2") (pinfunction "2_2") (pintype "passive"))
    )
    (net (code "17") (name "/FPGA_LED1_R") (class "Default")
      (node (ref "R87") (pin "2") (pinfunction "2_2") (pintype "passive"))
    )
    (net (code "18") (name "/FPGA_LED2_G") (class "Default")
      (node (ref "R92") (pin "2") (pinfunction "2_2") (pintype "passive"))
      (node (ref "SB1") (pin "1") (pinfunction "1_1") (pintype "passive"))
    )
    (net (code "19") (name "/FPGA_LED2_R") (class "Default")
      (node (ref "R95") (pin "2") (pinfunction "2_2") (pintype "passive"))
      (node (ref "SB2") (pin "1") (pinfunction "1_1") (pintype "passive"))
    )
    (net (code "20") (name "/FPGA_LED3_G") (class "Default")
      (node (ref "R97") (pin "2") (pinfunction "2_2") (pintype "passive"))
      (node (ref "SB3") (pin "1") (pinfunction "1_1") (pintype "passive"))
    )
    (net (code "21") (name "/FPGA_LED3_R") (class "Default")
      (node (ref "R99") (pin "2") (pinfunction "2_2") (pintype "passive"))
      (node (ref "SB4") (pin "1") (pinfunction "1_1") (pintype "passive"))
    )
    (net (code "22") (name "/FPGA_SPI_DAC_SS") (class "Default")
      (node (ref "IC11") (pin "1") (pinfunction "~{SYNC}_1") (pintype "input"))
      (node (ref "IC16") (pin "5") (pinfunction "~{SYN}C_5") (pintype "input"))
    )
    (net (code "23") (name "/FPGA_SPI_MOSI") (class "Default")
      (node (ref "IC11") (pin "3") (pinfunction "SDIN_3") (pintype "input"))
      (node (ref "IC16") (pin "7") (pinfunction "DIN_7") (pintype "input"))
    )
    (net (code "24") (name "/FPGA_SPI_SCLK") (class "Default")
      (node (ref "IC11") (pin "2") (pinfunction "SCLK_2") (pintype "input"))
      (node (ref "IC16") (pin "6") (pinfunction "SCLK_6") (pintype "input"))
    )
    (net (code "25") (name "/LM75_OS") (class "Default")
      (node (ref "IC10") (pin "3") (pinfunction "OS_3") (pintype "passive"))
      (node (ref "R62") (pin "1") (pinfunction "1_1") (pintype "passive"))
    )
    (net (code "26") (name "/LMK_CLK") (class "Default")
      (node (ref "IC9") (pin "13") (pinfunction "CLKout2_13") (pintype "passive"))
    )
    (net (code "27") (name "/PG_VCC1P1") (class "Default")
      (node (ref "IC13") (pin "3") (pinfunction "PG_3") (pintype "output"))
      (node (ref "R90") (pin "1") (pinfunction "1_1") (pintype "passive"))
    )
    (net (code "28") (name "/REF_CLK_IN") (class "Default")
      (node (ref "IC20") (pin "1") (pinfunction "B1_1") (pintype "passive"))
      (node (ref "J8") (pin "1") (pinfunction "X_1") (pintype "passive"))
    )
    (net (code "29") (name "/REF_CLK_OUT") (class "Default")
      (node (ref "IC9") (pin "17") (pinfunction "CLKout4_17") (pintype "passive"))
      (node (ref "J7") (pin "1") (pinfunction "X_1") (pintype "passive"))
    )
    (net (code "30") (name "/RxPLL_CLK") (class "Default")
      (node (ref "C160") (pin "2") (pinfunction "2_2") (pintype "passive"))
      (node (ref "R69") (pin "1") (pinfunction "1_1") (pintype "passive"))
    )
    (net (code "31") (name "/TCXO_DAC_VREF") (class "Default")
      (node (ref "C183") (pin "1") (pinfunction "1_1") (pintype "passive"))
      (node (ref "IC16") (pin "2") (pinfunction "Vref_2") (pintype "input"))
      (node (ref "R76") (pin "1") (pinfunction "1_1") (pintype "passive"))
      (node (ref "R78") (pin "2") (pinfunction "2_2") (pintype "passive"))
      (node (ref "R81") (pin "1") (pinfunction "1_1") (pintype "passive"))
      (node (ref "R83") (pin "1") (pinfunction "1_1") (pintype "passive"))
    )
    (net (code "32") (name "/TxPLL_CLK") (class "Default")
      (node (ref "C158") (pin "2") (pinfunction "2_2") (pintype "passive"))
      (node (ref "R65") (pin "1") (pinfunction "1_1") (pintype "passive"))
    )
    (net (code "33") (name "/XO_VC") (class "Default")
      (node (ref "C163") (pin "2") (pinfunction "2_2") (pintype "passive"))
      (node (ref "C184") (pin "1") (pinfunction "1_1") (pintype "passive"))
      (node (ref "IC16") (pin "3") (pinfunction "Vfb_3") (pintype "input"))
      (node (ref "IC16") (pin "4") (pinfunction "Vout_4") (pintype "output"))
      (node (ref "R71") (pin "1") (pinfunction "1_1") (pintype "passive"))
      (node (ref "R72") (pin "1") (pinfunction "1_1") (pintype "passive"))
      (node (ref "R73") (pin "1") (pinfunction "1_1") (pintype "passive"))
      (node (ref "XO1") (pin "1") (pinfunction "VCO_1") (pintype "input"))
    )
    (net (code "34") (name "GND") (class "Default")
      (node (ref "C156") (pin "2") (pinfunction "2_2") (pintype "passive"))
      (node (ref "C157") (pin "1") (pinfunction "1_1") (pintype "passive"))
      (node (ref "C158") (pin "1") (pinfunction "1_1") (pintype "passive"))
      (node (ref "C159") (pin "1") (pinfunction "1_1") (pintype "passive"))
      (node (ref "C160") (pin "1") (pinfunction "1_1") (pintype "passive"))
      (node (ref "C161") (pin "1") (pinfunction "1_1") (pintype "passive"))
      (node (ref "C162") (pin "1") (pinfunction "1_1") (pintype "passive"))
      (node (ref "C163") (pin "1") (pinfunction "1_1") (pintype "passive"))
      (node (ref "C164") (pin "1") (pinfunction "1_1") (pintype "passive"))
      (node (ref "C165") (pin "1") (pinfunction "1_1") (pintype "passive"))
      (node (ref "C166") (pin "1") (pinfunction "1_1") (pintype "passive"))
      (node (ref "C167") (pin "1") (pinfunction "1_1") (pintype "passive"))
      (node (ref "C168") (pin "1") (pinfunction "1_1") (pintype "passive"))
      (node (ref "C169") (pin "1") (pinfunction "1_1") (pintype "passive"))
      (node (ref "C170") (pin "1") (pinfunction "1_1") (pintype "passive"))
      (node (ref "C171") (pin "1") (pinfunction "1_1") (pintype "passive"))
      (node (ref "C172") (pin "1") (pinfunction "1_1") (pintype "passive"))
      (node (ref "C173") (pin "1") (pinfunction "1_1") (pintype "passive"))
      (node (ref "C174") (pin "2") (pinfunction "2_2") (pintype "passive"))
      (node (ref "C175") (pin "2") (pinfunction "2_2") (pintype "passive"))
      (node (ref "C176") (pin "1") (pinfunction "1_1") (pintype "passive"))
      (node (ref "C177") (pin "1") (pinfunction "1_1") (pintype "passive"))
      (node (ref "C178") (pin "1") (pinfunction "1_1") (pintype "passive"))
      (node (ref "C179") (pin "1") (pinfunction "1_1") (pintype "passive"))
      (node (ref "C180") (pin "2") (pinfunction "2_2") (pintype "passive"))
      (node (ref "C181") (pin "2") (pinfunction "2_2") (pintype "passive"))
      (node (ref "C182") (pin "2") (pinfunction "2_2") (pintype "passive"))
      (node (ref "C183") (pin "2") (pinfunction "2_2") (pintype "passive"))
      (node (ref "C184") (pin "2") (pinfunction "2_2") (pintype "passive"))
      (node (ref "C185") (pin "2") (pinfunction "2_2") (pintype "passive"))
      (node (ref "C186") (pin "1") (pinfunction "1_1") (pintype "passive"))
      (node (ref "C187") (pin "1") (pinfunction "1_1") (pintype "passive"))
      (node (ref "C188") (pin "1") (pinfunction "1_1") (pintype "passive"))
      (node (ref "C189") (pin "1") (pinfunction "1_1") (pintype "passive"))
      (node (ref "C190") (pin "1") (pinfunction "1_1") (pintype "passive"))
      (node (ref "C191") (pin "1") (pinfunction "1_1") (pintype "passive"))
      (node (ref "C192") (pin "1") (pinfunction "1_1") (pintype "passive"))
      (node (ref "C193") (pin "2") (pinfunction "2_2") (pintype "passive"))
      (node (ref "C194") (pin "1") (pinfunction "1_1") (pintype "passive"))
      (node (ref "C195") (pin "2") (pinfunction "2_2") (pintype "passive"))
      (node (ref "C196") (pin "1") (pinfunction "1_1") (pintype "passive"))
      (node (ref "C197") (pin "1") (pinfunction "1_1") (pintype "passive"))
      (node (ref "C198") (pin "1") (pinfunction "1_1") (pintype "passive"))
      (node (ref "C199") (pin "1") (pinfunction "1_1") (pintype "passive"))
      (node (ref "IC10") (pin "4") (pinfunction "GND_4") (pintype "passive"))
      (node (ref "IC10") (pin "5") (pinfunction "A2_5") (pintype "passive"))
      (node (ref "IC10") (pin "6") (pinfunction "A1_6") (pintype "passive"))
      (node (ref "IC10") (pin "7") (pinfunction "A0_7") (pintype "passive"))
      (node (ref "IC11") (pin "5") (pinfunction "GND_5") (pintype "power_in"))
      (node (ref "IC12") (pin "1") (pinfunction "E0_1") (pintype "input"))
      (node (ref "IC12") (pin "2") (pinfunction "E1_2") (pintype "input"))
      (node (ref "IC12") (pin "3") (pinfunction "E2_3") (pintype "input"))
      (node (ref "IC12") (pin "4") (pinfunction "VSS_4") (pintype "power_in"))
      (node (ref "IC12") (pin "7") (pinfunction "~{WC}_7") (pintype "input"))
      (node (ref "IC12") (pin "PAD") (pinfunction "PAD_PAD") (pintype "power_in"))
      (node (ref "IC13") (pin "2") (pinfunction "GND_2") (pintype "passive"))
      (node (ref "IC13") (pin "PAD") (pinfunction "PAD_PAD") (pintype "passive"))
      (node (ref "IC14") (pin "4") (pinfunction "SGND_4") (pintype "passive"))
      (node (ref "IC14") (pin "6") (pinfunction "PGND_6") (pintype "passive"))
      (node (ref "IC14") (pin "PAD") (pinfunction "PAD_(SGND)_PAD") (pintype "passive"))
      (node (ref "IC15") (pin "3") (pinfunction "W_3") (pintype "passive"))
      (node (ref "IC15") (pin "4") (pinfunction "GND_4") (pintype "passive"))
      (node (ref "IC15") (pin "PAD") (pinfunction "GND_PAD") (pintype "passive"))
      (node (ref "IC16") (pin "8") (pinfunction "GND_8") (pintype "passive"))
      (node (ref "IC17") (pin "3") (pinfunction "VSS_3") (pintype "power_in"))
      (node (ref "IC18") (pin "2") (pinfunction "GND_2") (pintype "passive"))
      (node (ref "IC18") (pin "PAD") (pinfunction "PAD_PAD") (pintype "passive"))
      (node (ref "IC19") (pin "4") (pinfunction "SGND_4") (pintype "passive"))
      (node (ref "IC19") (pin "6") (pinfunction "PGND_6") (pintype "passive"))
      (node (ref "IC19") (pin "PAD") (pinfunction "PAD_(SGND)_PAD") (pintype "passive"))
      (node (ref "IC20") (pin "2") (pinfunction "GND_2") (pintype "passive"))
      (node (ref "IC9") (pin "1") (pinfunction "GND_1") (pintype "passive"))
      (node (ref "IC9") (pin "11") (pinfunction "GND_11") (pintype "passive"))
      (node (ref "IC9") (pin "12") (pinfunction "GND_12") (pintype "passive"))
      (node (ref "IC9") (pin "16") (pinfunction "GND_16") (pintype "passive"))
      (node (ref "IC9") (pin "19") (pinfunction "GND_19") (pintype "passive"))
      (node (ref "IC9") (pin "22") (pinfunction "SEL_22") (pintype "passive"))
      (node (ref "IC9") (pin "25") (pinfunction "GND_25") (pintype "passive"))
      (node (ref "IC9") (pin "7") (pinfunction "GND_7") (pintype "passive"))
      (node (ref "J7") (pin "2") (pinfunction "Y_2") (pintype "passive"))
      (node (ref "J8") (pin "2") (pinfunction "Y_2") (pintype "passive"))
      (node (ref "R100") (pin "1") (pinfunction "1_1") (pintype "passive"))
      (node (ref "R67") (pin "1") (pinfunction "1_1") (pintype "passive"))
      (node (ref "R73") (pin "2") (pinfunction "2_2") (pintype "passive"))
      (node (ref "R80") (pin "2") (pinfunction "2_2") (pintype "passive"))
      (node (ref "R82") (pin "1") (pinfunction "1_1") (pintype "passive"))
      (node (ref "R83") (pin "2") (pinfunction "2_2") (pintype "passive"))
      (node (ref "R89") (pin "2") (pinfunction "2_2") (pintype "passive"))
      (node (ref "R91") (pin "1") (pinfunction "1_1") (pintype "passive"))
      (node (ref "VT4") (pin "S") (pinfunction "S_S") (pintype "passive"))
      (node (ref "XO1") (pin "4") (pinfunction "GND_4") (pintype "passive"))
    )
    (net (code "35") (name "Net-(C154-Pad1)") (class "Default")
      (node (ref "C154") (pin "1") (pinfunction "1_1") (pintype "passive"))
      (node (ref "C155") (pin "2") (pinfunction "2_2") (pintype "passive"))
      (node (ref "R67") (pin "2") (pinfunction "2_2") (pintype "passive"))
    )
    (net (code "36") (name "Net-(C159-Pad2)") (class "Default")
      (node (ref "C159") (pin "2") (pinfunction "2_2") (pintype "passive"))
      (node (ref "FR38") (pin "1") (pinfunction "1_1") (pintype "passive"))
      (node (ref "R64") (pin "1") (pinfunction "1_1") (pintype "passive"))
    )
    (net (code "37") (name "Net-(C195-Pad1)") (class "Default")
      (node (ref "C195") (pin "1") (pinfunction "1_1") (pintype "passive"))
      (node (ref "J9") (pin "2") (pinfunction "2_2") (pintype "passive"))
      (node (ref "R94") (pin "2") (pinfunction "2_2") (pintype "passive"))
      (node (ref "R96") (pin "2") (pinfunction "2_2") (pintype "passive"))
    )
    (net (code "38") (name "Net-(IC9-CLKin)") (class "Default")
      (node (ref "C155") (pin "1") (pinfunction "1_1") (pintype "passive"))
      (node (ref "IC9") (pin "21") (pinfunction "CLKin_21") (pintype "passive"))
    )
    (net (code "39") (name "Net-(IC9-CLKin*)") (class "Default")
      (node (ref "C162") (pin "2") (pinfunction "2_2") (pintype "passive"))
      (node (ref "IC9") (pin "20") (pinfunction "CLKin*_20") (pintype "passive"))
    )
    (net (code "40") (name "Net-(IC9-CLKout0)") (class "Default")
      (node (ref "IC9") (pin "3") (pinfunction "CLKout0_3") (pintype "passive"))
      (node (ref "R65") (pin "2") (pinfunction "2_2") (pintype "passive"))
    )
    (net (code "41") (name "Net-(IC9-CLKout1)") (class "Default")
      (node (ref "IC9") (pin "5") (pinfunction "CLKout1_5") (pintype "passive"))
      (node (ref "R69") (pin "2") (pinfunction "2_2") (pintype "passive"))
    )
    (net (code "42") (name "Net-(IC9-OE)") (class "Default")
      (node (ref "IC9") (pin "24") (pinfunction "OE_24") (pintype "passive"))
      (node (ref "R61") (pin "1") (pinfunction "1_1") (pintype "passive"))
    )
    (net (code "43") (name "Net-(IC11-VDD)") (class "Default")
      (node (ref "C175") (pin "1") (pinfunction "1_1") (pintype "passive"))
      (node (ref "FR41") (pin "2") (pinfunction "2_2") (pintype "passive"))
      (node (ref "IC11") (pin "4") (pinfunction "VDD_4") (pintype "power_in"))
    )
    (net (code "44") (name "Net-(IC11-VOUT)") (class "Default")
      (node (ref "IC11") (pin "6") (pinfunction "VOUT_6") (pintype "tri_state"))
      (node (ref "R72") (pin "2") (pinfunction "2_2") (pintype "passive"))
    )
    (net (code "45") (name "Net-(IC13-ADJ)") (class "Default")
      (node (ref "IC13") (pin "5") (pinfunction "ADJ_5") (pintype "input"))
      (node (ref "R74") (pin "1") (pinfunction "1_1") (pintype "passive"))
      (node (ref "R80") (pin "1") (pinfunction "1_1") (pintype "passive"))
    )
    (net (code "46") (name "Net-(IC14-VCON)") (class "Default")
      (node (ref "C182") (pin "1") (pinfunction "1_1") (pintype "passive"))
      (node (ref "IC14") (pin "2") (pinfunction "VCON_2") (pintype "input"))
      (node (ref "R79") (pin "1") (pinfunction "1_1") (pintype "passive"))
      (node (ref "R82") (pin "2") (pinfunction "2_2") (pintype "passive"))
    )
    (net (code "47") (name "Net-(IC14-VREF)") (class "Default")
      (node (ref "IC14") (pin "8") (pinfunction "VREF_8") (pintype "output"))
      (node (ref "R79") (pin "2") (pinfunction "2_2") (pintype "passive"))
    )
    (net (code "48") (name "Net-(IC16-Vdd)") (class "Default")
      (node (ref "C180") (pin "1") (pinfunction "1_1") (pintype "passive"))
      (node (ref "FR42") (pin "2") (pinfunction "2_2") (pintype "passive"))
      (node (ref "IC16") (pin "1") (pinfunction "Vdd_1") (pintype "power_in"))
      (node (ref "R76") (pin "2") (pinfunction "2_2") (pintype "passive"))
    )
    (net (code "49") (name "Net-(IC17-IN)") (class "Default")
      (node (ref "C185") (pin "1") (pinfunction "1_1") (pintype "passive"))
      (node (ref "C187") (pin "2") (pinfunction "2_2") (pintype "passive"))
      (node (ref "FR43") (pin "2") (pinfunction "2_2") (pintype "passive"))
      (node (ref "IC17") (pin "1") (pinfunction "IN_1") (pintype "power_in"))
    )
    (net (code "50") (name "Net-(IC18-ADJ)") (class "Default")
      (node (ref "IC18") (pin "5") (pinfunction "ADJ_5") (pintype "input"))
      (node (ref "R84") (pin "1") (pinfunction "1_1") (pintype "passive"))
      (node (ref "R89") (pin "1") (pinfunction "1_1") (pintype "passive"))
    )
    (net (code "51") (name "Net-(IC18-PG)") (class "Default")
      (node (ref "C192") (pin "2") (pinfunction "2_2") (pintype "passive"))
      (node (ref "IC18") (pin "3") (pinfunction "PG_3") (pintype "output"))
    )
    (net (code "52") (name "Net-(IC19-VCON)") (class "Default")
      (node (ref "C193") (pin "1") (pinfunction "1_1") (pintype "passive"))
      (node (ref "IC19") (pin "2") (pinfunction "VCON_2") (pintype "input"))
      (node (ref "R88") (pin "1") (pinfunction "1_1") (pintype "passive"))
      (node (ref "R91") (pin "2") (pinfunction "2_2") (pintype "passive"))
    )
    (net (code "53") (name "Net-(IC19-VREF)") (class "Default")
      (node (ref "IC19") (pin "8") (pinfunction "VREF_8") (pintype "output"))
      (node (ref "R88") (pin "2") (pinfunction "2_2") (pintype "passive"))
    )
    (net (code "54") (name "Net-(IC20-A)") (class "Default")
      (node (ref "C154") (pin "2") (pinfunction "2_2") (pintype "passive"))
      (node (ref "IC20") (pin "4") (pinfunction "A_4") (pintype "passive"))
    )
    (net (code "55") (name "Net-(IC20-B0)") (class "Default")
      (node (ref "IC20") (pin "3") (pinfunction "B0_3") (pintype "passive"))
      (node (ref "XO1") (pin "6") (pinfunction "RF_OUT_6") (pintype "output"))
    )
    (net (code "56") (name "Net-(J9-Pad1)") (class "Default")
      (node (ref "J9") (pin "1") (pinfunction "1_1") (pintype "passive"))
      (node (ref "R100") (pin "2") (pinfunction "2_2") (pintype "passive"))
      (node (ref "VT4") (pin "D") (pinfunction "D_D") (pintype "passive"))
    )
    (net (code "57") (name "Net-(LED1-Pad3)") (class "Default")
      (node (ref "LED1") (pin "3") (pinfunction "3_3") (pintype "power_in"))
      (node (ref "R85") (pin "1") (pinfunction "1_1") (pintype "passive"))
    )
    (net (code "58") (name "Net-(LED1-Pad4)") (class "Default")
      (node (ref "LED1") (pin "4") (pinfunction "4_4") (pintype "power_in"))
      (node (ref "R87") (pin "1") (pinfunction "1_1") (pintype "passive"))
    )
    (net (code "59") (name "Net-(LED2-Pad3)") (class "Default")
      (node (ref "LED2") (pin "3") (pinfunction "3_3") (pintype "power_in"))
      (node (ref "R92") (pin "1") (pinfunction "1_1") (pintype "passive"))
    )
    (net (code "60") (name "Net-(LED2-Pad4)") (class "Default")
      (node (ref "LED2") (pin "4") (pinfunction "4_4") (pintype "power_in"))
      (node (ref "R95") (pin "1") (pinfunction "1_1") (pintype "passive"))
    )
    (net (code "61") (name "Net-(LED3-Pad3)") (class "Default")
      (node (ref "LED3") (pin "3") (pinfunction "3_3") (pintype "power_in"))
      (node (ref "R97") (pin "1") (pinfunction "1_1") (pintype "passive"))
    )
    (net (code "62") (name "Net-(LED3-Pad4)") (class "Default")
      (node (ref "LED3") (pin "4") (pinfunction "4_4") (pintype "power_in"))
      (node (ref "R99") (pin "1") (pinfunction "1_1") (pintype "passive"))
    )
    (net (code "63") (name "Net-(XO1-VC_FILTER)") (class "Default")
      (node (ref "C157") (pin "2") (pinfunction "2_2") (pintype "passive"))
      (node (ref "XO1") (pin "7") (pinfunction "VC_FILTER_7") (pintype "input"))
    )
    (net (code "64") (name "VCC1P1") (class "Default")
      (node (ref "C179") (pin "2") (pinfunction "2_2") (pintype "passive"))
      (node (ref "IC13") (pin "4") (pinfunction "Vout_4") (pintype "output"))
      (node (ref "R74") (pin "2") (pinfunction "2_2") (pintype "passive"))
    )
    (net (code "65") (name "VCC1P8") (class "Default")
      (node (ref "C177") (pin "2") (pinfunction "2_2") (pintype "passive"))
      (node (ref "C178") (pin "2") (pinfunction "2_2") (pintype "passive"))
      (node (ref "FR40") (pin "1") (pinfunction "1_1") (pintype "passive"))
      (node (ref "IC13") (pin "1") (pinfunction "EN_1") (pintype "input"))
      (node (ref "IC13") (pin "6") (pinfunction "Vin_6") (pintype "input"))
      (node (ref "IC14") (pin "3") (pinfunction "FB_3") (pintype "input"))
      (node (ref "IC14") (pin "5") (pinfunction "VOUT_5") (pintype "output"))
      (node (ref "R62") (pin "2") (pinfunction "2_2") (pintype "passive"))
      (node (ref "R93") (pin "2") (pinfunction "2_2") (pintype "passive"))
    )
    (net (code "66") (name "VCC2P5") (class "Default")
      (node (ref "C191") (pin "2") (pinfunction "2_2") (pintype "passive"))
      (node (ref "IC18") (pin "4") (pinfunction "Vout_4") (pintype "output"))
      (node (ref "R81") (pin "2") (pinfunction "2_2") (pintype "passive"))
      (node (ref "R84") (pin "2") (pinfunction "2_2") (pintype "passive"))
      (node (ref "R98") (pin "1") (pinfunction "1_1") (pintype "passive"))
    )
    (net (code "67") (name "VCC2P5_VREF") (class "Default")
      (node (ref "C186") (pin "2") (pinfunction "2_2") (pintype "passive"))
      (node (ref "IC17") (pin "2") (pinfunction "OUT_2") (pintype "power_in"))
      (node (ref "R78") (pin "1") (pinfunction "1_1") (pintype "passive"))
    )
    (net (code "68") (name "VCC3P3") (class "Default")
      (node (ref "C156") (pin "1") (pinfunction "1_1") (pintype "passive"))
      (node (ref "C174") (pin "1") (pinfunction "1_1") (pintype "passive"))
      (node (ref "C181") (pin "1") (pinfunction "1_1") (pintype "passive"))
      (node (ref "C189") (pin "2") (pinfunction "2_2") (pintype "passive"))
      (node (ref "C190") (pin "2") (pinfunction "2_2") (pintype "passive"))
      (node (ref "FR44") (pin "1") (pinfunction "1_1") (pintype "passive"))
      (node (ref "IC10") (pin "8") (pinfunction "VCC_8") (pintype "passive"))
      (node (ref "IC12") (pin "8") (pinfunction "VCC_8") (pintype "power_in"))
      (node (ref "IC15") (pin "7") (pinfunction "HOLD_7") (pintype "passive"))
      (node (ref "IC15") (pin "8") (pinfunction "VCC_8") (pintype "passive"))
      (node (ref "IC18") (pin "1") (pinfunction "EN_1") (pintype "input"))
      (node (ref "IC18") (pin "6") (pinfunction "Vin_6") (pintype "input"))
      (node (ref "IC19") (pin "3") (pinfunction "FB_3") (pintype "input"))
      (node (ref "IC19") (pin "5") (pinfunction "VOUT_5") (pintype "output"))
      (node (ref "LED1") (pin "1") (pinfunction "1_1") (pintype "power_in"))
      (node (ref "LED1") (pin "2") (pinfunction "2_2") (pintype "power_in"))
      (node (ref "LED2") (pin "1") (pinfunction "1_1") (pintype "power_in"))
      (node (ref "LED2") (pin "2") (pinfunction "2_2") (pintype "power_in"))
      (node (ref "LED3") (pin "1") (pinfunction "1_1") (pintype "power_in"))
      (node (ref "LED3") (pin "2") (pinfunction "2_2") (pintype "power_in"))
      (node (ref "R101") (pin "1") (pinfunction "1_1") (pintype "passive"))
      (node (ref "R68") (pin "1") (pinfunction "1_1") (pintype "passive"))
      (node (ref "R70") (pin "1") (pinfunction "1_1") (pintype "passive"))
      (node (ref "R75") (pin "2") (pinfunction "2_2") (pintype "passive"))
      (node (ref "R77") (pin "2") (pinfunction "2_2") (pintype "passive"))
      (node (ref "R96") (pin "1") (pinfunction "1_1") (pintype "passive"))
    )
    (net (code "69") (name "VCC3P3_CLK") (class "Default")
      (node (ref "C196") (pin "2") (pinfunction "2_2") (pintype "passive"))
      (node (ref "C199") (pin "2") (pinfunction "2_2") (pintype "passive"))
      (node (ref "FR39") (pin "1") (pinfunction "1_1") (pintype "passive"))
      (node (ref "FR41") (pin "1") (pinfunction "1_1") (pintype "passive"))
      (node (ref "FR42") (pin "1") (pinfunction "1_1") (pintype "passive"))
      (node (ref "FR43") (pin "1") (pinfunction "1_1") (pintype "passive"))
      (node (ref "FR44") (pin "2") (pinfunction "2_2") (pintype "passive"))
      (node (ref "IC20") (pin "5") (pinfunction "VCC_5") (pintype "passive"))
      (node (ref "R64") (pin "2") (pinfunction "2_2") (pintype "passive"))
    )
    (net (code "70") (name "VCC3P3_XO") (class "Default")
      (node (ref "C161") (pin "2") (pinfunction "2_2") (pintype "passive"))
      (node (ref "FR38") (pin "2") (pinfunction "2_2") (pintype "passive"))
      (node (ref "R71") (pin "2") (pinfunction "2_2") (pintype "passive"))
      (node (ref "XO1") (pin "9") (pinfunction "VCC_9") (pintype "power_in"))
    )
    (net (code "71") (name "VCC5P0") (class "Default")
      (node (ref "C176") (pin "2") (pinfunction "2_2") (pintype "passive"))
      (node (ref "C188") (pin "2") (pinfunction "2_2") (pintype "passive"))
      (node (ref "IC14") (pin "1") (pinfunction "EN_1") (pintype "input"))
      (node (ref "IC14") (pin "7") (pinfunction "VIN_7") (pintype "input"))
      (node (ref "IC19") (pin "7") (pinfunction "VIN_7") (pintype "input"))
      (node (ref "R86") (pin "2") (pinfunction "2_2") (pintype "passive"))
      (node (ref "R94") (pin "1") (pinfunction "1_1") (pintype "passive"))
    )
    (net (code "72") (name "VDIO_LMS") (class "Default")
      (node (ref "C198") (pin "2") (pinfunction "2_2") (pintype "passive"))
      (node (ref "FR45") (pin "2") (pinfunction "2_2") (pintype "passive"))
    )
    (net (code "73") (name "VDIO_LMS_FPGA") (class "Default")
      (node (ref "C197") (pin "2") (pinfunction "2_2") (pintype "passive"))
      (node (ref "FR45") (pin "1") (pinfunction "1_1") (pintype "passive"))
      (node (ref "R101") (pin "2") (pinfunction "2_2") (pintype "passive"))
      (node (ref "R98") (pin "2") (pinfunction "2_2") (pintype "passive"))
    )
    (net (code "74") (name "unconnected-(IC9-CLKout3-Pad15)") (class "Default")
      (node (ref "IC9") (pin "15") (pinfunction "CLKout3_15") (pintype "passive+no_connect"))
    )
    (net (code "75") (name "unconnected-(IC9-OSCin-Pad9)") (class "Default")
      (node (ref "IC9") (pin "9") (pinfunction "OSCin_9") (pintype "passive+no_connect"))
    )
    (net (code "76") (name "unconnected-(IC9-OSCout-Pad10)") (class "Default")
      (node (ref "IC9") (pin "10") (pinfunction "OSCout_10") (pintype "passive+no_connect"))
    )
    (net (code "77") (name "unconnected-(XO1-NC-Pad2)") (class "Default")
      (node (ref "XO1") (pin "2") (pinfunction "NC_2") (pintype "passive+no_connect"))
    )
    (net (code "78") (name "unconnected-(XO1-NC-Pad3)") (class "Default")
      (node (ref "XO1") (pin "3") (pinfunction "NC_3") (pintype "passive+no_connect"))
    )
    (net (code "79") (name "unconnected-(XO1-NC-Pad5)") (class "Default")
      (node (ref "XO1") (pin "5") (pinfunction "NC_5") (pintype "passive+no_connect"))
    )
    (net (code "80") (name "unconnected-(XO1-NC-Pad8)") (class "Default")
      (node (ref "XO1") (pin "8") (pinfunction "NC_8") (pintype "passive+no_connect"))
    )
    (net (code "81") (name "unconnected-(XO1-NC-Pad10)") (class "Default")
      (node (ref "XO1") (pin "10") (pinfunction "NC_10") (pintype "passive+no_connect"))
    )
  )
)
